# tappytap.net
KiCad netlist of a schematic drawn in EAGLE
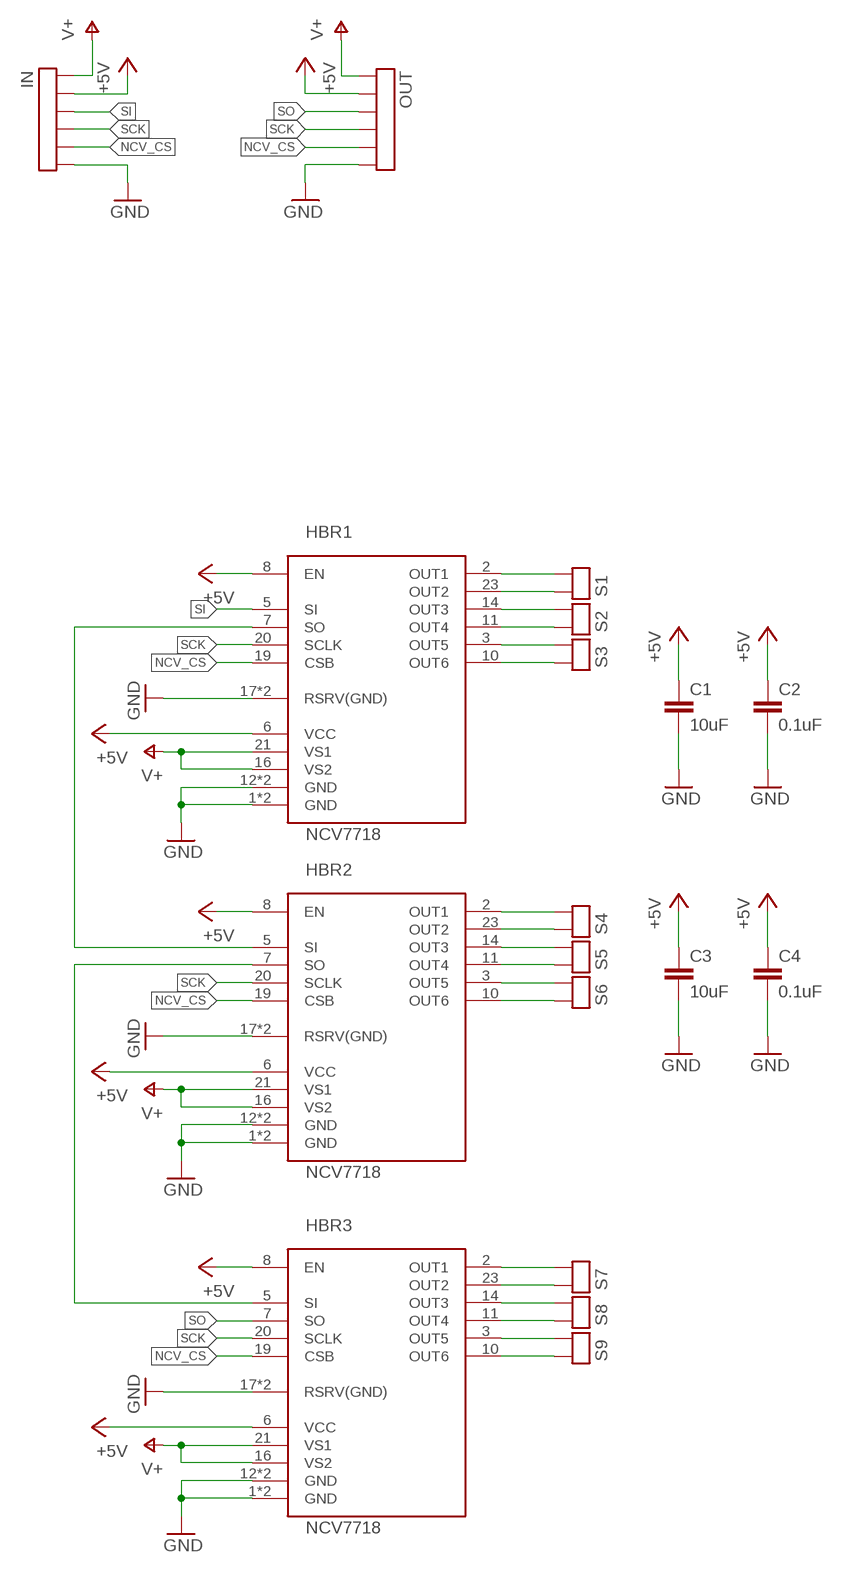
[diagram p0: schematic, sheet 1]

(export (version "E")
  (design (tool "Eeschema 10.0.6"))
  (components
    (comp (ref "C1")
      (value "10uF")
      (footprint "eagle-import:C0603")
      (libsource (lib "eagle-import") (part "C-EUC0603"))
    )
    (comp (ref "C2")
      (value "0.1uF")
      (footprint "eagle-import:C0603")
      (libsource (lib "eagle-import") (part "C-EUC0603"))
    )
    (comp (ref "C3")
      (value "10uF")
      (footprint "eagle-import:C0603")
      (libsource (lib "eagle-import") (part "C-EUC0603"))
    )
    (comp (ref "C4")
      (value "0.1uF")
      (footprint "eagle-import:C0603")
      (libsource (lib "eagle-import") (part "C-EUC0603"))
    )
    (comp (ref "HBR1")
      (value "NCV7718")
      (footprint "eagle-import:SSOP-24")
      (libsource (lib "eagle-import") (part "NCV7718"))
    )
    (comp (ref "HBR2")
      (value "NCV7718")
      (footprint "eagle-import:SSOP-24")
      (libsource (lib "eagle-import") (part "NCV7718"))
    )
    (comp (ref "HBR3")
      (value "NCV7718")
      (footprint "eagle-import:SSOP-24")
      (libsource (lib "eagle-import") (part "NCV7718"))
    )
    (comp (ref "IN")
      (value "TP6")
      (footprint "eagle-import:TP6_2MM")
      (libsource (lib "eagle-import") (part "TP6"))
    )
    (comp (ref "OUT")
      (value "TP6")
      (footprint "eagle-import:TP6_2MM")
      (libsource (lib "eagle-import") (part "TP6"))
    )
    (comp (ref "S1")
      (value "TP2")
      (footprint "eagle-import:TP2_2MM")
      (libsource (lib "eagle-import") (part "TP2"))
    )
    (comp (ref "S2")
      (value "TP2")
      (footprint "eagle-import:TP2_2MM")
      (libsource (lib "eagle-import") (part "TP2"))
    )
    (comp (ref "S3")
      (value "TP2")
      (footprint "eagle-import:TP2_2MM")
      (libsource (lib "eagle-import") (part "TP2"))
    )
    (comp (ref "S4")
      (value "TP2")
      (footprint "eagle-import:TP2_2MM")
      (libsource (lib "eagle-import") (part "TP2"))
    )
    (comp (ref "S5")
      (value "TP2")
      (footprint "eagle-import:TP2_2MM")
      (libsource (lib "eagle-import") (part "TP2"))
    )
    (comp (ref "S6")
      (value "TP2")
      (footprint "eagle-import:TP2_2MM")
      (libsource (lib "eagle-import") (part "TP2"))
    )
    (comp (ref "S7")
      (value "TP2")
      (footprint "eagle-import:TP2_2MM")
      (libsource (lib "eagle-import") (part "TP2"))
    )
    (comp (ref "S8")
      (value "TP2")
      (footprint "eagle-import:TP2_2MM")
      (libsource (lib "eagle-import") (part "TP2"))
    )
    (comp (ref "S9")
      (value "TP2")
      (footprint "eagle-import:TP2_2MM")
      (libsource (lib "eagle-import") (part "TP2"))
    )
  )
  (nets
    (net (code "1") (name "+5V") (class "Default")
      (node (ref "C1") (pin "1") (pinfunction "1_1") (pintype "passive"))
      (node (ref "C2") (pin "1") (pinfunction "1_1") (pintype "passive"))
      (node (ref "C3") (pin "1") (pinfunction "1_1") (pintype "passive"))
      (node (ref "C4") (pin "1") (pinfunction "1_1") (pintype "passive"))
      (node (ref "HBR1") (pin "6") (pinfunction "VCC_6") (pintype "bidirectional"))
      (node (ref "HBR1") (pin "8") (pinfunction "EN_8") (pintype "bidirectional"))
      (node (ref "HBR2") (pin "6") (pinfunction "VCC_6") (pintype "bidirectional"))
      (node (ref "HBR2") (pin "8") (pinfunction "EN_8") (pintype "bidirectional"))
      (node (ref "HBR3") (pin "6") (pinfunction "VCC_6") (pintype "bidirectional"))
      (node (ref "HBR3") (pin "8") (pinfunction "EN_8") (pintype "bidirectional"))
      (node (ref "IN") (pin "P$5") (pinfunction "5_P$5") (pintype "bidirectional"))
      (node (ref "OUT") (pin "P$5") (pinfunction "5_P$5") (pintype "bidirectional"))
    )
    (net (code "2") (name "GND") (class "Default")
      (node (ref "C1") (pin "2") (pinfunction "2_2") (pintype "passive"))
      (node (ref "C2") (pin "2") (pinfunction "2_2") (pintype "passive"))
      (node (ref "C3") (pin "2") (pinfunction "2_2") (pintype "passive"))
      (node (ref "C4") (pin "2") (pinfunction "2_2") (pintype "passive"))
      (node (ref "HBR1") (pin "1") (pinfunction "GND_1") (pintype "bidirectional"))
      (node (ref "HBR1") (pin "12") (pinfunction "GND_12") (pintype "bidirectional"))
      (node (ref "HBR1") (pin "13") (pinfunction "GND_13") (pintype "bidirectional"))
      (node (ref "HBR1") (pin "17") (pinfunction "RSRV(GND)_17") (pintype "bidirectional"))
      (node (ref "HBR1") (pin "18") (pinfunction "RSRV(GND)_18") (pintype "bidirectional"))
      (node (ref "HBR1") (pin "24") (pinfunction "GND_24") (pintype "bidirectional"))
      (node (ref "HBR2") (pin "1") (pinfunction "GND_1") (pintype "bidirectional"))
      (node (ref "HBR2") (pin "12") (pinfunction "GND_12") (pintype "bidirectional"))
      (node (ref "HBR2") (pin "13") (pinfunction "GND_13") (pintype "bidirectional"))
      (node (ref "HBR2") (pin "17") (pinfunction "RSRV(GND)_17") (pintype "bidirectional"))
      (node (ref "HBR2") (pin "18") (pinfunction "RSRV(GND)_18") (pintype "bidirectional"))
      (node (ref "HBR2") (pin "24") (pinfunction "GND_24") (pintype "bidirectional"))
      (node (ref "HBR3") (pin "1") (pinfunction "GND_1") (pintype "bidirectional"))
      (node (ref "HBR3") (pin "12") (pinfunction "GND_12") (pintype "bidirectional"))
      (node (ref "HBR3") (pin "13") (pinfunction "GND_13") (pintype "bidirectional"))
      (node (ref "HBR3") (pin "17") (pinfunction "RSRV(GND)_17") (pintype "bidirectional"))
      (node (ref "HBR3") (pin "18") (pinfunction "RSRV(GND)_18") (pintype "bidirectional"))
      (node (ref "HBR3") (pin "24") (pinfunction "GND_24") (pintype "bidirectional"))
      (node (ref "IN") (pin "P$1") (pinfunction "1_P$1") (pintype "bidirectional"))
      (node (ref "OUT") (pin "P$1") (pinfunction "1_P$1") (pintype "bidirectional"))
    )
    (net (code "3") (name "NCV_CS") (class "Default")
      (node (ref "HBR1") (pin "19") (pinfunction "CSB_19") (pintype "bidirectional"))
      (node (ref "HBR2") (pin "19") (pinfunction "CSB_19") (pintype "bidirectional"))
      (node (ref "HBR3") (pin "19") (pinfunction "CSB_19") (pintype "bidirectional"))
      (node (ref "IN") (pin "P$2") (pinfunction "2_P$2") (pintype "bidirectional"))
      (node (ref "OUT") (pin "P$2") (pinfunction "2_P$2") (pintype "bidirectional"))
    )
    (net (code "4") (name "Net-(HBR1-OUT1)") (class "Default")
      (node (ref "HBR1") (pin "2") (pinfunction "OUT1_2") (pintype "bidirectional"))
      (node (ref "S1") (pin "P$1") (pinfunction "0_P$1") (pintype "bidirectional"))
    )
    (net (code "5") (name "Net-(HBR1-OUT2)") (class "Default")
      (node (ref "HBR1") (pin "23") (pinfunction "OUT2_23") (pintype "bidirectional"))
      (node (ref "S1") (pin "P$2") (pinfunction "1_P$2") (pintype "bidirectional"))
    )
    (net (code "6") (name "Net-(HBR1-OUT3)") (class "Default")
      (node (ref "HBR1") (pin "14") (pinfunction "OUT3_14") (pintype "bidirectional"))
      (node (ref "S2") (pin "P$1") (pinfunction "0_P$1") (pintype "bidirectional"))
    )
    (net (code "7") (name "Net-(HBR1-OUT4)") (class "Default")
      (node (ref "HBR1") (pin "11") (pinfunction "OUT4_11") (pintype "bidirectional"))
      (node (ref "S2") (pin "P$2") (pinfunction "1_P$2") (pintype "bidirectional"))
    )
    (net (code "8") (name "Net-(HBR1-OUT5)") (class "Default")
      (node (ref "HBR1") (pin "3") (pinfunction "OUT5_3") (pintype "bidirectional"))
      (node (ref "S3") (pin "P$1") (pinfunction "0_P$1") (pintype "bidirectional"))
    )
    (net (code "9") (name "Net-(HBR1-OUT6)") (class "Default")
      (node (ref "HBR1") (pin "10") (pinfunction "OUT6_10") (pintype "bidirectional"))
      (node (ref "S3") (pin "P$2") (pinfunction "1_P$2") (pintype "bidirectional"))
    )
    (net (code "10") (name "Net-(HBR1-SO)") (class "Default")
      (node (ref "HBR1") (pin "7") (pinfunction "SO_7") (pintype "bidirectional"))
      (node (ref "HBR2") (pin "5") (pinfunction "SI_5") (pintype "bidirectional"))
    )
    (net (code "11") (name "Net-(HBR2-OUT1)") (class "Default")
      (node (ref "HBR2") (pin "2") (pinfunction "OUT1_2") (pintype "bidirectional"))
      (node (ref "S4") (pin "P$1") (pinfunction "0_P$1") (pintype "bidirectional"))
    )
    (net (code "12") (name "Net-(HBR2-OUT2)") (class "Default")
      (node (ref "HBR2") (pin "23") (pinfunction "OUT2_23") (pintype "bidirectional"))
      (node (ref "S4") (pin "P$2") (pinfunction "1_P$2") (pintype "bidirectional"))
    )
    (net (code "13") (name "Net-(HBR2-OUT3)") (class "Default")
      (node (ref "HBR2") (pin "14") (pinfunction "OUT3_14") (pintype "bidirectional"))
      (node (ref "S5") (pin "P$1") (pinfunction "0_P$1") (pintype "bidirectional"))
    )
    (net (code "14") (name "Net-(HBR2-OUT4)") (class "Default")
      (node (ref "HBR2") (pin "11") (pinfunction "OUT4_11") (pintype "bidirectional"))
      (node (ref "S5") (pin "P$2") (pinfunction "1_P$2") (pintype "bidirectional"))
    )
    (net (code "15") (name "Net-(HBR2-OUT5)") (class "Default")
      (node (ref "HBR2") (pin "3") (pinfunction "OUT5_3") (pintype "bidirectional"))
      (node (ref "S6") (pin "P$1") (pinfunction "0_P$1") (pintype "bidirectional"))
    )
    (net (code "16") (name "Net-(HBR2-OUT6)") (class "Default")
      (node (ref "HBR2") (pin "10") (pinfunction "OUT6_10") (pintype "bidirectional"))
      (node (ref "S6") (pin "P$2") (pinfunction "1_P$2") (pintype "bidirectional"))
    )
    (net (code "17") (name "Net-(HBR2-SO)") (class "Default")
      (node (ref "HBR2") (pin "7") (pinfunction "SO_7") (pintype "bidirectional"))
      (node (ref "HBR3") (pin "5") (pinfunction "SI_5") (pintype "bidirectional"))
    )
    (net (code "18") (name "Net-(HBR3-OUT1)") (class "Default")
      (node (ref "HBR3") (pin "2") (pinfunction "OUT1_2") (pintype "bidirectional"))
      (node (ref "S7") (pin "P$1") (pinfunction "0_P$1") (pintype "bidirectional"))
    )
    (net (code "19") (name "Net-(HBR3-OUT2)") (class "Default")
      (node (ref "HBR3") (pin "23") (pinfunction "OUT2_23") (pintype "bidirectional"))
      (node (ref "S7") (pin "P$2") (pinfunction "1_P$2") (pintype "bidirectional"))
    )
    (net (code "20") (name "Net-(HBR3-OUT3)") (class "Default")
      (node (ref "HBR3") (pin "14") (pinfunction "OUT3_14") (pintype "bidirectional"))
      (node (ref "S8") (pin "P$1") (pinfunction "0_P$1") (pintype "bidirectional"))
    )
    (net (code "21") (name "Net-(HBR3-OUT4)") (class "Default")
      (node (ref "HBR3") (pin "11") (pinfunction "OUT4_11") (pintype "bidirectional"))
      (node (ref "S8") (pin "P$2") (pinfunction "1_P$2") (pintype "bidirectional"))
    )
    (net (code "22") (name "Net-(HBR3-OUT5)") (class "Default")
      (node (ref "HBR3") (pin "3") (pinfunction "OUT5_3") (pintype "bidirectional"))
      (node (ref "S9") (pin "P$1") (pinfunction "0_P$1") (pintype "bidirectional"))
    )
    (net (code "23") (name "Net-(HBR3-OUT6)") (class "Default")
      (node (ref "HBR3") (pin "10") (pinfunction "OUT6_10") (pintype "bidirectional"))
      (node (ref "S9") (pin "P$2") (pinfunction "1_P$2") (pintype "bidirectional"))
    )
    (net (code "24") (name "SCK") (class "Default")
      (node (ref "HBR1") (pin "20") (pinfunction "SCLK_20") (pintype "bidirectional"))
      (node (ref "HBR2") (pin "20") (pinfunction "SCLK_20") (pintype "bidirectional"))
      (node (ref "HBR3") (pin "20") (pinfunction "SCLK_20") (pintype "bidirectional"))
      (node (ref "IN") (pin "P$3") (pinfunction "3_P$3") (pintype "bidirectional"))
      (node (ref "OUT") (pin "P$3") (pinfunction "3_P$3") (pintype "bidirectional"))
    )
    (net (code "25") (name "SI") (class "Default")
      (node (ref "HBR1") (pin "5") (pinfunction "SI_5") (pintype "bidirectional"))
      (node (ref "IN") (pin "P$4") (pinfunction "4_P$4") (pintype "bidirectional"))
    )
    (net (code "26") (name "SO") (class "Default")
      (node (ref "HBR3") (pin "7") (pinfunction "SO_7") (pintype "bidirectional"))
      (node (ref "OUT") (pin "P$4") (pinfunction "4_P$4") (pintype "bidirectional"))
    )
    (net (code "27") (name "V+") (class "Default")
      (node (ref "HBR1") (pin "16") (pinfunction "VS2_16") (pintype "bidirectional"))
      (node (ref "HBR1") (pin "21") (pinfunction "VS1_21") (pintype "bidirectional"))
      (node (ref "HBR2") (pin "16") (pinfunction "VS2_16") (pintype "bidirectional"))
      (node (ref "HBR2") (pin "21") (pinfunction "VS1_21") (pintype "bidirectional"))
      (node (ref "HBR3") (pin "16") (pinfunction "VS2_16") (pintype "bidirectional"))
      (node (ref "HBR3") (pin "21") (pinfunction "VS1_21") (pintype "bidirectional"))
      (node (ref "IN") (pin "P$6") (pinfunction "6_P$6") (pintype "bidirectional"))
      (node (ref "OUT") (pin "P$6") (pinfunction "6_P$6") (pintype "bidirectional"))
    )
  )
)
